# CPU_Dev_revA_1.net
KiCad netlist of a schematic drawn in EAGLE
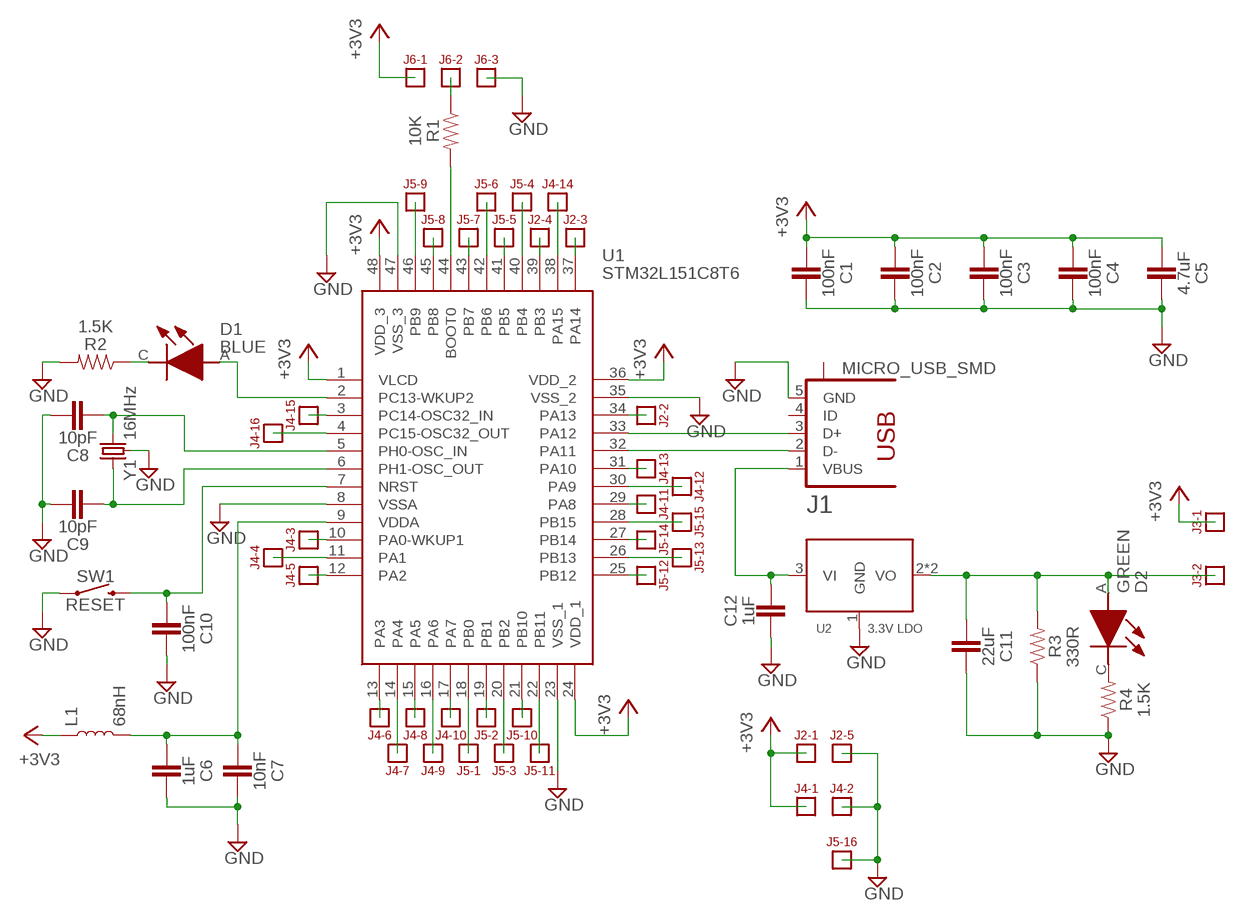
[diagram p0: schematic, sheet 1]

(export (version "E")
  (design (tool "Eeschema 10.0.6"))
  (components
    (comp (ref "C1")
      (value "100nF")
      (footprint "eagle-import:0402")
      (libsource (lib "eagle-import") (part "C_0402"))
    )
    (comp (ref "C2")
      (value "100nF")
      (footprint "eagle-import:0402")
      (libsource (lib "eagle-import") (part "C_0402"))
    )
    (comp (ref "C3")
      (value "100nF")
      (footprint "eagle-import:0402")
      (libsource (lib "eagle-import") (part "C_0402"))
    )
    (comp (ref "C4")
      (value "100nF")
      (footprint "eagle-import:0402")
      (libsource (lib "eagle-import") (part "C_0402"))
    )
    (comp (ref "C5")
      (value "4.7uF")
      (footprint "eagle-import:0402")
      (libsource (lib "eagle-import") (part "C_0402"))
    )
    (comp (ref "C6")
      (value "1uF")
      (footprint "eagle-import:0402")
      (libsource (lib "eagle-import") (part "C_0402"))
    )
    (comp (ref "C7")
      (value "10nF")
      (footprint "eagle-import:0402")
      (libsource (lib "eagle-import") (part "C_0402"))
    )
    (comp (ref "C8")
      (value "10pF")
      (footprint "eagle-import:0402")
      (libsource (lib "eagle-import") (part "C_0402"))
    )
    (comp (ref "C9")
      (value "10pF")
      (footprint "eagle-import:0402")
      (libsource (lib "eagle-import") (part "C_0402"))
    )
    (comp (ref "C10")
      (value "100nF")
      (footprint "eagle-import:0402")
      (libsource (lib "eagle-import") (part "C_0402"))
    )
    (comp (ref "C11")
      (value "22uF")
      (footprint "eagle-import:1206")
      (libsource (lib "eagle-import") (part "C_1206"))
    )
    (comp (ref "C12")
      (value "1uF")
      (footprint "eagle-import:0402")
      (libsource (lib "eagle-import") (part "C_0402"))
    )
    (comp (ref "D1")
      (value "BLUE")
      (footprint "eagle-import:LED_0603")
      (libsource (lib "eagle-import") (part "LED_0603"))
    )
    (comp (ref "D2")
      (value "GREEN")
      (footprint "eagle-import:LED_0603")
      (libsource (lib "eagle-import") (part "LED_0603"))
    )
    (comp (ref "J1")
      (value "MICRO_USB_SMD")
      (footprint "eagle-import:10118192-0002LF")
      (libsource (lib "eagle-import") (part "MICRO_USB_SMD"))
    )
    (comp (ref "J2")
      (value "HEADER_5PIN")
      (footprint "eagle-import:HEADER_5PIN")
      (libsource (lib "eagle-import") (part "HEADER_5PIN"))
    )
    (comp (ref "J3")
      (value "HEADER_2PIN")
      (footprint "eagle-import:HEADER_2PIN")
      (libsource (lib "eagle-import") (part "HEADER_2PIN"))
    )
    (comp (ref "J4")
      (value "HEADER_16PIN")
      (footprint "eagle-import:HEADER_16PIN")
      (libsource (lib "eagle-import") (part "HEADER_16PIN"))
    )
    (comp (ref "J5")
      (value "HEADER_16PIN")
      (footprint "eagle-import:HEADER_16PIN")
      (libsource (lib "eagle-import") (part "HEADER_16PIN"))
    )
    (comp (ref "J6")
      (value "HEADER_3PIN")
      (footprint "eagle-import:HEADER_3PIN")
      (libsource (lib "eagle-import") (part "HEADER_3PIN"))
    )
    (comp (ref "L1")
      (value "68nH")
      (footprint "eagle-import:0603")
      (libsource (lib "eagle-import") (part "L_0603"))
    )
    (comp (ref "R1")
      (value "10K")
      (footprint "eagle-import:0402")
      (libsource (lib "eagle-import") (part "R_0402"))
    )
    (comp (ref "R2")
      (value "1.5K")
      (footprint "eagle-import:0402")
      (libsource (lib "eagle-import") (part "R_0402"))
    )
    (comp (ref "R3")
      (value "330R")
      (footprint "eagle-import:0402")
      (libsource (lib "eagle-import") (part "R_0402"))
    )
    (comp (ref "R4")
      (value "1.5K")
      (footprint "eagle-import:0402")
      (libsource (lib "eagle-import") (part "R_0402"))
    )
    (comp (ref "SW1")
      (value "RESET")
      (footprint "eagle-import:PUSHBUTTON_SMD")
      (libsource (lib "eagle-import") (part "PUSHBUTTON_SMD"))
    )
    (comp (ref "U1")
      (value "STM32L151C8T6")
      (footprint "eagle-import:LQFP-48_7X7")
      (fields (field (name "MOUSER_PART_NUMBER") "511-STM32L151C8T6"))
      (libsource (lib "eagle-import") (part "STM32L151C8T6"))
    )
    (comp (ref "U2")
      (value "3.3V LDO")
      (footprint "eagle-import:SOT223")
      (libsource (lib "eagle-import") (part "VREG_SOT223"))
    )
    (comp (ref "Y1")
      (value "16MHz")
      (footprint "eagle-import:SMD3225-4P")
      (libsource (lib "eagle-import") (part "XTAL_SMD3225-4P"))
    )
  )
  (nets
    (net (code "1") (name "+3V3") (class "Default")
      (node (ref "C1") (pin "1") (pinfunction "1_1") (pintype "passive"))
      (node (ref "C2") (pin "1") (pinfunction "1_1") (pintype "passive"))
      (node (ref "C3") (pin "1") (pinfunction "1_1") (pintype "passive"))
      (node (ref "C4") (pin "1") (pinfunction "1_1") (pintype "passive"))
      (node (ref "C5") (pin "1") (pinfunction "1_1") (pintype "passive"))
      (node (ref "J2") (pin "P$1") (pinfunction "P$1_P$1") (pintype "bidirectional"))
      (node (ref "J3") (pin "P$1") (pinfunction "P$1_P$1") (pintype "bidirectional"))
      (node (ref "J4") (pin "P$1") (pinfunction "P$1_P$1") (pintype "bidirectional"))
      (node (ref "J6") (pin "P$1") (pinfunction "P$1_P$1") (pintype "bidirectional"))
      (node (ref "L1") (pin "1") (pinfunction "1_1") (pintype "passive"))
      (node (ref "U1") (pin "1") (pinfunction "VLCD_1") (pintype "bidirectional"))
      (node (ref "U1") (pin "24") (pinfunction "VDD_1_24") (pintype "bidirectional"))
      (node (ref "U1") (pin "36") (pinfunction "VDD_2_36") (pintype "bidirectional"))
      (node (ref "U1") (pin "48") (pinfunction "VDD_3_48") (pintype "bidirectional"))
    )
    (net (code "2") (name "GND") (class "Default")
      (node (ref "C1") (pin "2") (pinfunction "2_2") (pintype "passive"))
      (node (ref "C10") (pin "2") (pinfunction "2_2") (pintype "passive"))
      (node (ref "C11") (pin "2") (pinfunction "2_2") (pintype "passive"))
      (node (ref "C12") (pin "1") (pinfunction "1_1") (pintype "passive"))
      (node (ref "C2") (pin "2") (pinfunction "2_2") (pintype "passive"))
      (node (ref "C3") (pin "2") (pinfunction "2_2") (pintype "passive"))
      (node (ref "C4") (pin "2") (pinfunction "2_2") (pintype "passive"))
      (node (ref "C5") (pin "2") (pinfunction "2_2") (pintype "passive"))
      (node (ref "C6") (pin "2") (pinfunction "2_2") (pintype "passive"))
      (node (ref "C7") (pin "2") (pinfunction "2_2") (pintype "passive"))
      (node (ref "C8") (pin "2") (pinfunction "2_2") (pintype "passive"))
      (node (ref "C9") (pin "2") (pinfunction "2_2") (pintype "passive"))
      (node (ref "J1") (pin "5") (pinfunction "GND_5") (pintype "passive"))
      (node (ref "J2") (pin "P$5") (pinfunction "P$1_P$5") (pintype "bidirectional"))
      (node (ref "J4") (pin "P$2") (pinfunction "P$1_P$2") (pintype "bidirectional"))
      (node (ref "J5") (pin "P$16") (pinfunction "P$1_P$16") (pintype "bidirectional"))
      (node (ref "J6") (pin "P$3") (pinfunction "P$1_P$3") (pintype "bidirectional"))
      (node (ref "R2") (pin "2") (pinfunction "2_2") (pintype "passive"))
      (node (ref "R3") (pin "1") (pinfunction "1_1") (pintype "passive"))
      (node (ref "R4") (pin "1") (pinfunction "1_1") (pintype "passive"))
      (node (ref "SW1") (pin "A1") (pinfunction "1_A1") (pintype "passive"))
      (node (ref "U1") (pin "23") (pinfunction "VSS_1_23") (pintype "bidirectional"))
      (node (ref "U1") (pin "35") (pinfunction "VSS_2_35") (pintype "bidirectional"))
      (node (ref "U1") (pin "47") (pinfunction "VSS_3_47") (pintype "bidirectional"))
      (node (ref "U1") (pin "8") (pinfunction "VSSA_8") (pintype "bidirectional"))
      (node (ref "U2") (pin "1") (pinfunction "GND_1") (pintype "bidirectional"))
      (node (ref "Y1") (pin "2") (pinfunction "3_2") (pintype "passive"))
      (node (ref "Y1") (pin "4") (pinfunction "3_4") (pintype "passive"))
    )
    (net (code "3") (name "Net-(D1-K)") (class "Default")
      (node (ref "D1") (pin "C") (pinfunction "K_C") (pintype "bidirectional"))
      (node (ref "R2") (pin "1") (pinfunction "1_1") (pintype "passive"))
    )
    (net (code "4") (name "Net-(D2-K)") (class "Default")
      (node (ref "D2") (pin "C") (pinfunction "K_C") (pintype "bidirectional"))
      (node (ref "R4") (pin "2") (pinfunction "2_2") (pintype "passive"))
    )
    (net (code "5") (name "Net-(J1-D+)") (class "Default")
      (node (ref "J1") (pin "3") (pinfunction "D+_3") (pintype "passive"))
      (node (ref "U1") (pin "33") (pinfunction "PA12_33") (pintype "bidirectional"))
    )
    (net (code "6") (name "Net-(J1-D-)") (class "Default")
      (node (ref "J1") (pin "2") (pinfunction "D-_2") (pintype "passive"))
      (node (ref "U1") (pin "32") (pinfunction "PA11_32") (pintype "bidirectional"))
    )
    (net (code "7") (name "Net-(J1-VBUS)") (class "Default")
      (node (ref "C12") (pin "2") (pinfunction "2_2") (pintype "passive"))
      (node (ref "J1") (pin "1") (pinfunction "VBUS_1") (pintype "passive"))
      (node (ref "U2") (pin "3") (pinfunction "VI_3") (pintype "bidirectional"))
    )
    (net (code "8") (name "Net-(J2B-P$1)") (class "Default")
      (node (ref "J2") (pin "P$2") (pinfunction "P$1_P$2") (pintype "bidirectional"))
      (node (ref "U1") (pin "34") (pinfunction "PA13_34") (pintype "bidirectional"))
    )
    (net (code "9") (name "Net-(J2C-P$1)") (class "Default")
      (node (ref "J2") (pin "P$3") (pinfunction "P$1_P$3") (pintype "bidirectional"))
      (node (ref "U1") (pin "37") (pinfunction "PA14_37") (pintype "bidirectional"))
    )
    (net (code "10") (name "Net-(J2D-P$1)") (class "Default")
      (node (ref "J2") (pin "P$4") (pinfunction "P$1_P$4") (pintype "bidirectional"))
      (node (ref "U1") (pin "39") (pinfunction "PB3_39") (pintype "bidirectional"))
    )
    (net (code "11") (name "Net-(J3B-P$1)") (class "Default")
      (node (ref "C11") (pin "1") (pinfunction "1_1") (pintype "passive"))
      (node (ref "D2") (pin "A") (pinfunction "A_A") (pintype "bidirectional"))
      (node (ref "J3") (pin "P$2") (pinfunction "P$1_P$2") (pintype "bidirectional"))
      (node (ref "R3") (pin "2") (pinfunction "2_2") (pintype "passive"))
      (node (ref "U2") (pin "2") (pinfunction "VO_2") (pintype "bidirectional"))
      (node (ref "U2") (pin "4") (pinfunction "VO_4") (pintype "bidirectional"))
    )
    (net (code "12") (name "Net-(J4B-P$1)") (class "Default")
      (node (ref "J4") (pin "P$10") (pinfunction "P$1_P$10") (pintype "bidirectional"))
      (node (ref "U1") (pin "17") (pinfunction "PA7_17") (pintype "bidirectional"))
    )
    (net (code "13") (name "Net-(J4C-P$1)") (class "Default")
      (node (ref "J4") (pin "P$11") (pinfunction "P$1_P$11") (pintype "bidirectional"))
      (node (ref "U1") (pin "29") (pinfunction "PA8_29") (pintype "bidirectional"))
    )
    (net (code "14") (name "Net-(J4D-P$1)") (class "Default")
      (node (ref "J4") (pin "P$12") (pinfunction "P$1_P$12") (pintype "bidirectional"))
      (node (ref "U1") (pin "30") (pinfunction "PA9_30") (pintype "bidirectional"))
    )
    (net (code "15") (name "Net-(J4E-P$1)") (class "Default")
      (node (ref "J4") (pin "P$13") (pinfunction "P$1_P$13") (pintype "bidirectional"))
      (node (ref "U1") (pin "31") (pinfunction "PA10_31") (pintype "bidirectional"))
    )
    (net (code "16") (name "Net-(J4F-P$1)") (class "Default")
      (node (ref "J4") (pin "P$14") (pinfunction "P$1_P$14") (pintype "bidirectional"))
      (node (ref "U1") (pin "38") (pinfunction "PA15_38") (pintype "bidirectional"))
    )
    (net (code "17") (name "Net-(J4G-P$1)") (class "Default")
      (node (ref "J4") (pin "P$15") (pinfunction "P$1_P$15") (pintype "bidirectional"))
      (node (ref "U1") (pin "3") (pinfunction "PC14-OSC32_IN_3") (pintype "bidirectional"))
    )
    (net (code "18") (name "Net-(J4H-P$1)") (class "Default")
      (node (ref "J4") (pin "P$16") (pinfunction "P$1_P$16") (pintype "bidirectional"))
      (node (ref "U1") (pin "4") (pinfunction "PC15-OSC32_OUT_4") (pintype "bidirectional"))
    )
    (net (code "19") (name "Net-(J4J-P$1)") (class "Default")
      (node (ref "J4") (pin "P$3") (pinfunction "P$1_P$3") (pintype "bidirectional"))
      (node (ref "U1") (pin "10") (pinfunction "PA0-WKUP1_10") (pintype "bidirectional"))
    )
    (net (code "20") (name "Net-(J4K-P$1)") (class "Default")
      (node (ref "J4") (pin "P$4") (pinfunction "P$1_P$4") (pintype "bidirectional"))
      (node (ref "U1") (pin "11") (pinfunction "PA1_11") (pintype "bidirectional"))
    )
    (net (code "21") (name "Net-(J4L-P$1)") (class "Default")
      (node (ref "J4") (pin "P$5") (pinfunction "P$1_P$5") (pintype "bidirectional"))
      (node (ref "U1") (pin "12") (pinfunction "PA2_12") (pintype "bidirectional"))
    )
    (net (code "22") (name "Net-(J4M-P$1)") (class "Default")
      (node (ref "J4") (pin "P$6") (pinfunction "P$1_P$6") (pintype "bidirectional"))
      (node (ref "U1") (pin "13") (pinfunction "PA3_13") (pintype "bidirectional"))
    )
    (net (code "23") (name "Net-(J4N-P$1)") (class "Default")
      (node (ref "J4") (pin "P$7") (pinfunction "P$1_P$7") (pintype "bidirectional"))
      (node (ref "U1") (pin "14") (pinfunction "PA4_14") (pintype "bidirectional"))
    )
    (net (code "24") (name "Net-(J4O-P$1)") (class "Default")
      (node (ref "J4") (pin "P$8") (pinfunction "P$1_P$8") (pintype "bidirectional"))
      (node (ref "U1") (pin "15") (pinfunction "PA5_15") (pintype "bidirectional"))
    )
    (net (code "25") (name "Net-(J4P-P$1)") (class "Default")
      (node (ref "J4") (pin "P$9") (pinfunction "P$1_P$9") (pintype "bidirectional"))
      (node (ref "U1") (pin "16") (pinfunction "PA6_16") (pintype "bidirectional"))
    )
    (net (code "26") (name "Net-(J5B-P$1)") (class "Default")
      (node (ref "J5") (pin "P$10") (pinfunction "P$1_P$10") (pintype "bidirectional"))
      (node (ref "U1") (pin "21") (pinfunction "PB10_21") (pintype "bidirectional"))
    )
    (net (code "27") (name "Net-(J5C-P$1)") (class "Default")
      (node (ref "J5") (pin "P$11") (pinfunction "P$1_P$11") (pintype "bidirectional"))
      (node (ref "U1") (pin "22") (pinfunction "PB11_22") (pintype "bidirectional"))
    )
    (net (code "28") (name "Net-(J5D-P$1)") (class "Default")
      (node (ref "J5") (pin "P$12") (pinfunction "P$1_P$12") (pintype "bidirectional"))
      (node (ref "U1") (pin "25") (pinfunction "PB12_25") (pintype "bidirectional"))
    )
    (net (code "29") (name "Net-(J5E-P$1)") (class "Default")
      (node (ref "J5") (pin "P$13") (pinfunction "P$1_P$13") (pintype "bidirectional"))
      (node (ref "U1") (pin "26") (pinfunction "PB13_26") (pintype "bidirectional"))
    )
    (net (code "30") (name "Net-(J5F-P$1)") (class "Default")
      (node (ref "J5") (pin "P$14") (pinfunction "P$1_P$14") (pintype "bidirectional"))
      (node (ref "U1") (pin "27") (pinfunction "PB14_27") (pintype "bidirectional"))
    )
    (net (code "31") (name "Net-(J5G-P$1)") (class "Default")
      (node (ref "J5") (pin "P$15") (pinfunction "P$1_P$15") (pintype "bidirectional"))
      (node (ref "U1") (pin "28") (pinfunction "PB15_28") (pintype "bidirectional"))
    )
    (net (code "32") (name "Net-(J5I-P$1)") (class "Default")
      (node (ref "J5") (pin "P$2") (pinfunction "P$1_P$2") (pintype "bidirectional"))
      (node (ref "U1") (pin "19") (pinfunction "PB1_19") (pintype "bidirectional"))
    )
    (net (code "33") (name "Net-(J5J-P$1)") (class "Default")
      (node (ref "J5") (pin "P$3") (pinfunction "P$1_P$3") (pintype "bidirectional"))
      (node (ref "U1") (pin "20") (pinfunction "PB2_20") (pintype "bidirectional"))
    )
    (net (code "34") (name "Net-(J5K-P$1)") (class "Default")
      (node (ref "J5") (pin "P$4") (pinfunction "P$1_P$4") (pintype "bidirectional"))
      (node (ref "U1") (pin "40") (pinfunction "PB4_40") (pintype "bidirectional"))
    )
    (net (code "35") (name "Net-(J5L-P$1)") (class "Default")
      (node (ref "J5") (pin "P$5") (pinfunction "P$1_P$5") (pintype "bidirectional"))
      (node (ref "U1") (pin "41") (pinfunction "PB5_41") (pintype "bidirectional"))
    )
    (net (code "36") (name "Net-(J5M-P$1)") (class "Default")
      (node (ref "J5") (pin "P$6") (pinfunction "P$1_P$6") (pintype "bidirectional"))
      (node (ref "U1") (pin "42") (pinfunction "PB6_42") (pintype "bidirectional"))
    )
    (net (code "37") (name "Net-(J5N-P$1)") (class "Default")
      (node (ref "J5") (pin "P$7") (pinfunction "P$1_P$7") (pintype "bidirectional"))
      (node (ref "U1") (pin "43") (pinfunction "PB7_43") (pintype "bidirectional"))
    )
    (net (code "38") (name "Net-(J5O-P$1)") (class "Default")
      (node (ref "J5") (pin "P$8") (pinfunction "P$1_P$8") (pintype "bidirectional"))
      (node (ref "U1") (pin "45") (pinfunction "PB8_45") (pintype "bidirectional"))
    )
    (net (code "39") (name "Net-(J5P-P$1)") (class "Default")
      (node (ref "J5") (pin "P$9") (pinfunction "P$1_P$9") (pintype "bidirectional"))
      (node (ref "U1") (pin "46") (pinfunction "PB9_46") (pintype "bidirectional"))
    )
    (net (code "40") (name "Net-(J6B-P$1)") (class "Default")
      (node (ref "J6") (pin "P$2") (pinfunction "P$1_P$2") (pintype "bidirectional"))
      (node (ref "R1") (pin "1") (pinfunction "1_1") (pintype "passive"))
    )
    (net (code "41") (name "Net-(SW1-2)") (class "Default")
      (node (ref "C10") (pin "1") (pinfunction "1_1") (pintype "passive"))
      (node (ref "SW1") (pin "B1") (pinfunction "2_B1") (pintype "passive"))
      (node (ref "U1") (pin "7") (pinfunction "NRST_7") (pintype "bidirectional"))
    )
    (net (code "42") (name "Net-(U1-BOOT0)") (class "Default")
      (node (ref "R1") (pin "2") (pinfunction "2_2") (pintype "passive"))
      (node (ref "U1") (pin "44") (pinfunction "BOOT0_44") (pintype "bidirectional"))
    )
    (net (code "43") (name "Net-(U1-PB0)") (class "Default")
      (node (ref "J5") (pin "P$1") (pinfunction "P$1_P$1") (pintype "bidirectional"))
      (node (ref "U1") (pin "18") (pinfunction "PB0_18") (pintype "bidirectional"))
    )
    (net (code "44") (name "Net-(U1-PC13-WKUP2)") (class "Default")
      (node (ref "D1") (pin "A") (pinfunction "A_A") (pintype "bidirectional"))
      (node (ref "U1") (pin "2") (pinfunction "PC13-WKUP2_2") (pintype "bidirectional"))
    )
    (net (code "45") (name "Net-(U1-PH0-OSC_IN)") (class "Default")
      (node (ref "C8") (pin "1") (pinfunction "1_1") (pintype "passive"))
      (node (ref "U1") (pin "5") (pinfunction "PH0-OSC_IN_5") (pintype "bidirectional"))
      (node (ref "Y1") (pin "3") (pinfunction "2_3") (pintype "passive"))
    )
    (net (code "46") (name "Net-(U1-PH1-OSC_OUT)") (class "Default")
      (node (ref "C9") (pin "1") (pinfunction "1_1") (pintype "passive"))
      (node (ref "U1") (pin "6") (pinfunction "PH1-OSC_OUT_6") (pintype "bidirectional"))
      (node (ref "Y1") (pin "1") (pinfunction "1_1") (pintype "passive"))
    )
    (net (code "47") (name "Net-(U1-VDDA)") (class "Default")
      (node (ref "C6") (pin "1") (pinfunction "1_1") (pintype "passive"))
      (node (ref "C7") (pin "1") (pinfunction "1_1") (pintype "passive"))
      (node (ref "L1") (pin "2") (pinfunction "2_2") (pintype "passive"))
      (node (ref "U1") (pin "9") (pinfunction "VDDA_9") (pintype "bidirectional"))
    )
    (net (code "48") (name "unconnected-(J1-ID-Pad4)") (class "Default")
      (node (ref "J1") (pin "4") (pinfunction "ID_4") (pintype "passive"))
    )
    (net (code "49") (name "unconnected-(J1-PadS1)") (class "Default")
      (node (ref "J1") (pin "S1") (pinfunction "S1_S1") (pintype "passive"))
    )
  )
)
